# DIONYSUS_SPI_FLASH_Dave_McCoy_s_conflict.net
KiCad netlist of a schematic drawn in Altium Designer
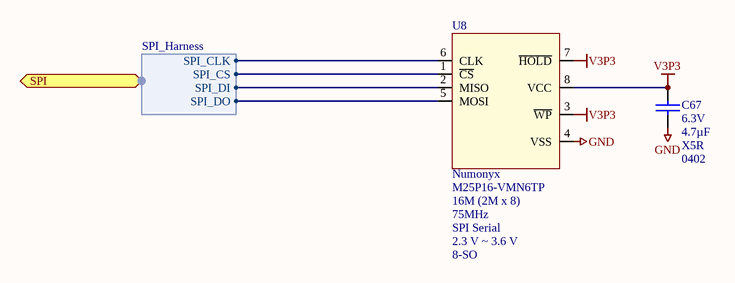
[diagram p0: DIONYSUS_SPI_FLASH (Dave McCoy's conflicted copy 2013-01-04).SchDoc]

(export (version "E")
  (design (tool "Eeschema 10.0.6"))
  (components
    (comp (ref "C67")
      (value "4.7uF")
      (footprint "C_ERA-0402")
      (description "CAP CER 4.7UF 6.3V X5R 0402")
      (fields
        (field (name "MANUFACTURER") "Murata Electronics North America")
        (field (name "MANUFACTURER PART NUMBER") "GRM155R60J475ME87D")
        (field (name "VOLTAGE - RATED") "6.3V")
        (field (name "CAPACITANCE") "4.7µF")
        (field (name "TEMPERATURE COEFFICIENT") "X5R")
        (field (name "PACKAGE / CASE") "0402")
      )
      (libsource (lib "Main LibraryX") (part "C_0402_4.7UF"))
    )
    (comp (ref "U8")
      (value "U_16MBIT_SPI_FLASH")
      (footprint "SOIC127P600X135-8L")
      (description "IC FLASH 16MBIT 75MHZ 8SOIC")
      (fields
        (field (name "MANUFACTURER") "Numonyx")
        (field (name "MANUFACTURER PART NUMBER") "M25P16-VMN6TP")
        (field (name "MEMORY SIZE") "16M (2M x 8)")
        (field (name "SPEED") "75MHz")
        (field (name "INTERFACE") "SPI Serial")
        (field (name "VOLTAGE - SUPPLY") "2.3 V ~ 3.6 V")
        (field (name "SUPPLIER DEVICE PACKAGE") "8-SO")
      )
      (libsource (lib "Main Library") (part "U_16MBIT_SPI_FLASH"))
    )
  )
  (nets
    (net (code "2") (name "/SPI_CLK") (class "Default")
      (node (ref "U8") (pin "6") (pinfunction "CLK_6") (pintype "passive"))
    )
    (net (code "3") (name "/SPI_CS") (class "Default")
      (node (ref "U8") (pin "1") (pinfunction "~{CS}_1") (pintype "passive"))
    )
    (net (code "4") (name "/SPI_DI") (class "Default")
      (node (ref "U8") (pin "2") (pinfunction "MISO_2") (pintype "passive"))
    )
    (net (code "5") (name "/SPI_DO") (class "Default")
      (node (ref "U8") (pin "5") (pinfunction "MOSI_5") (pintype "passive"))
    )
    (net (code "7") (name "GND") (class "Default")
      (node (ref "C67") (pin "1") (pinfunction "1_1") (pintype "passive"))
      (node (ref "U8") (pin "4") (pinfunction "VSS_4") (pintype "passive"))
    )
    (net (code "8") (name "V3P3") (class "Default")
      (node (ref "C67") (pin "2") (pinfunction "2_2") (pintype "passive"))
      (node (ref "U8") (pin "3") (pinfunction "~{WP}_3") (pintype "passive"))
      (node (ref "U8") (pin "7") (pinfunction "~{HOLD}_7") (pintype "passive"))
      (node (ref "U8") (pin "8") (pinfunction "VCC_8") (pintype "passive"))
    )
  )
)
